# Power_Measurement.net
KiCad netlist of a schematic drawn in Altium Designer
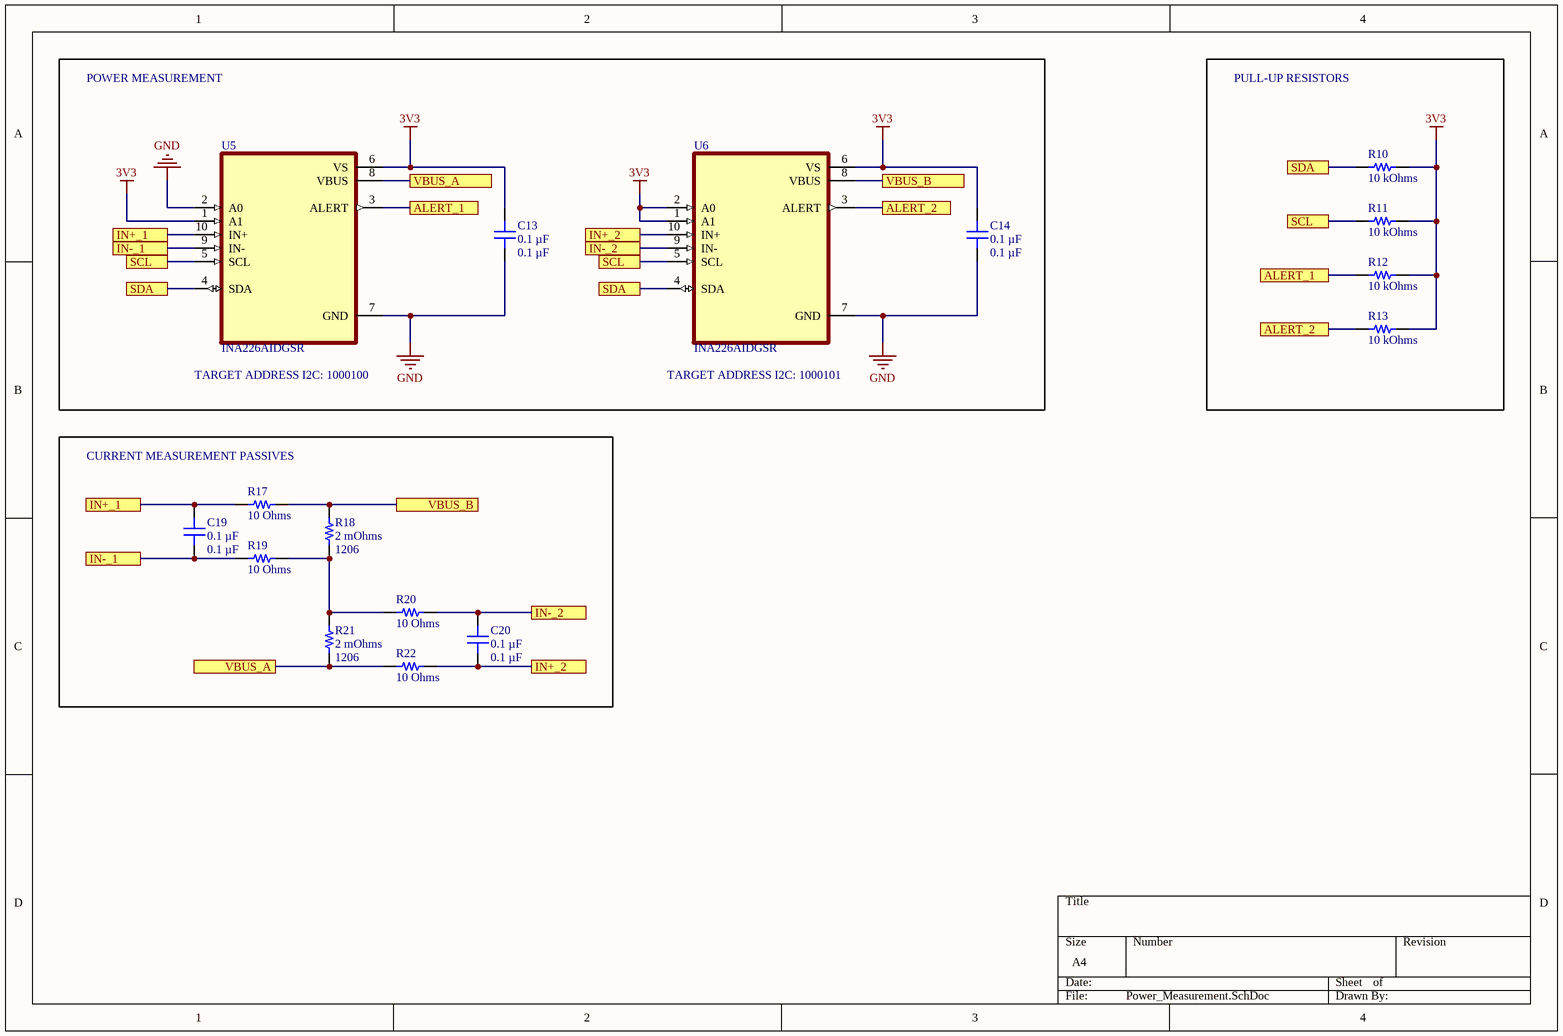
[diagram p0: Power_Measurement.SchDoc]

(export (version "E")
  (design (tool "Eeschema 10.0.6"))
  (components
    (comp (ref "C13")
      (value "0.1 µF")
      (footprint "CAP 0603_1608")
      (description "CAP CER 0.1UF 50V X7R 0603")
      (fields
        (field (name "PART NUMBER") "C0603C104K5RAC7411")
        (field (name "ALTIUM_VALUE") "0.1 µF")
        (field (name "MANUFACTURER") "KEMET")
      )
      (libsource (lib "Celestial Altium Library - altium_library") (part "Capacitor"))
    )
    (comp (ref "C14")
      (value "0.1 µF")
      (footprint "CAP 0603_1608")
      (description "CAP CER 0.1UF 50V X7R 0603")
      (fields
        (field (name "PART NUMBER") "C0603C104K5RAC7411")
        (field (name "ALTIUM_VALUE") "0.1 µF")
        (field (name "MANUFACTURER") "KEMET")
      )
      (libsource (lib "Celestial Altium Library - altium_library") (part "Capacitor"))
    )
    (comp (ref "C19")
      (value "0.1 µF")
      (footprint "CAP 0603_1608")
      (description "CAP CER 0.1UF 50V X7R 0603")
      (fields
        (field (name "PART NUMBER") "C0603C104K5RAC7411")
        (field (name "ALTIUM_VALUE") "0.1 µF")
        (field (name "MANUFACTURER") "KEMET")
      )
      (libsource (lib "Celestial Altium Library - altium_library") (part "Capacitor"))
    )
    (comp (ref "C20")
      (value "0.1 µF")
      (footprint "CAP 0603_1608")
      (description "CAP CER 0.1UF 50V X7R 0603")
      (fields
        (field (name "PART NUMBER") "C0603C104K5RAC7411")
        (field (name "ALTIUM_VALUE") "0.1 µF")
        (field (name "MANUFACTURER") "KEMET")
      )
      (libsource (lib "Celestial Altium Library - altium_library") (part "Capacitor"))
    )
    (comp (ref "R10")
      (value "10 kOhms")
      (footprint "RES 0603_1608")
      (description "RES 10K OHM 0.1% 1/16W 0603")
      (fields
        (field (name "PART NUMBER") "RNCS0603BKE10K0")
        (field (name "MANUFACTURER") "Stackpole Electronics Inc")
      )
      (libsource (lib "Celestial Altium Library - altium_library") (part "Resistor"))
    )
    (comp (ref "R11")
      (value "10 kOhms")
      (footprint "RES 0603_1608")
      (description "RES 10K OHM 0.1% 1/16W 0603")
      (fields
        (field (name "PART NUMBER") "RNCS0603BKE10K0")
        (field (name "MANUFACTURER") "Stackpole Electronics Inc")
      )
      (libsource (lib "Celestial Altium Library - altium_library") (part "Resistor"))
    )
    (comp (ref "R12")
      (value "10 kOhms")
      (footprint "RES 0603_1608")
      (description "RES 10K OHM 0.1% 1/16W 0603")
      (fields
        (field (name "PART NUMBER") "RNCS0603BKE10K0")
        (field (name "MANUFACTURER") "Stackpole Electronics Inc")
      )
      (libsource (lib "Celestial Altium Library - altium_library") (part "Resistor"))
    )
    (comp (ref "R13")
      (value "10 kOhms")
      (footprint "RES 0603_1608")
      (description "RES 10K OHM 0.1% 1/16W 0603")
      (fields
        (field (name "PART NUMBER") "RNCS0603BKE10K0")
        (field (name "MANUFACTURER") "Stackpole Electronics Inc")
      )
      (libsource (lib "Celestial Altium Library - altium_library") (part "Resistor"))
    )
    (comp (ref "R17")
      (value "10 Ohms")
      (footprint "RES 0603_1608")
      (description "RES SMD 10 OHM 0.1% 1/10W 0603")
      (fields (field (name "PART NUMBER") "CRT0603-BY-10R0ELF") (field (name "MANUFACTURER") "Bourns Inc."))
      (libsource (lib "Celestial Altium Library - altium_library") (part "Resistor"))
    )
    (comp (ref "R18")
      (value "2 mOhms")
      (footprint "STACKPOLE CSR1206")
      (description "1W 0.002 OHMS 1% 1206")
      (fields
        (field (name "PART NUMBER") "PCS1206FR0020ET")
        (field (name "PACKAGE / CASE") "1206")
        (field (name "MANUFACTURER") "Ohmite")
      )
      (libsource (lib "Celestial Altium Library - altium_library") (part "Resistor"))
    )
    (comp (ref "R19")
      (value "10 Ohms")
      (footprint "RES 0603_1608")
      (description "RES SMD 10 OHM 0.1% 1/10W 0603")
      (fields (field (name "PART NUMBER") "CRT0603-BY-10R0ELF") (field (name "MANUFACTURER") "Bourns Inc."))
      (libsource (lib "Celestial Altium Library - altium_library") (part "Resistor"))
    )
    (comp (ref "R20")
      (value "10 Ohms")
      (footprint "RES 0603_1608")
      (description "RES SMD 10 OHM 0.1% 1/10W 0603")
      (fields (field (name "PART NUMBER") "CRT0603-BY-10R0ELF") (field (name "MANUFACTURER") "Bourns Inc."))
      (libsource (lib "Celestial Altium Library - altium_library") (part "Resistor"))
    )
    (comp (ref "R21")
      (value "2 mOhms")
      (footprint "STACKPOLE CSR1206")
      (description "1W 0.002 OHMS 1% 1206")
      (fields
        (field (name "PART NUMBER") "PCS1206FR0020ET")
        (field (name "PACKAGE / CASE") "1206")
        (field (name "MANUFACTURER") "Ohmite")
      )
      (libsource (lib "Celestial Altium Library - altium_library") (part "Resistor"))
    )
    (comp (ref "R22")
      (value "10 Ohms")
      (footprint "RES 0603_1608")
      (description "RES SMD 10 OHM 0.1% 1/10W 0603")
      (fields (field (name "PART NUMBER") "CRT0603-BY-10R0ELF") (field (name "MANUFACTURER") "Bourns Inc."))
      (libsource (lib "Celestial Altium Library - altium_library") (part "Resistor"))
    )
    (comp (ref "U5")
      (value "INA226AIDGSR")
      (footprint "INA226AIDGSR:SOP50P490X110-10N")
      (fields (field (name "MF") "{'manufacturer': u'Texas Instruments'}"))
      (libsource (lib "*") (part "INA226AIDGSR"))
    )
    (comp (ref "U6")
      (value "INA226AIDGSR")
      (footprint "INA226AIDGSR:SOP50P490X110-10N")
      (fields (field (name "MF") "{'manufacturer': u'Texas Instruments'}"))
      (libsource (lib "*") (part "INA226AIDGSR"))
    )
  )
  (nets
    (net (code "1") (name "/ALERT_1") (class "Default")
      (node (ref "R12") (pin "2") (pinfunction "2_2") (pintype "passive"))
      (node (ref "U5") (pin "3") (pinfunction "ALERT_3") (pintype "output"))
    )
    (net (code "2") (name "/ALERT_2") (class "Default")
      (node (ref "R13") (pin "2") (pinfunction "2_2") (pintype "passive"))
      (node (ref "U6") (pin "3") (pinfunction "ALERT_3") (pintype "output"))
    )
    (net (code "3") (name "/IN+_1") (class "Default")
      (node (ref "C19") (pin "2") (pinfunction "2_2") (pintype "passive"))
      (node (ref "R17") (pin "2") (pinfunction "2_2") (pintype "passive"))
      (node (ref "U5") (pin "10") (pinfunction "IN+_10") (pintype "input"))
    )
    (net (code "4") (name "/IN+_2") (class "Default")
      (node (ref "C20") (pin "2") (pinfunction "2_2") (pintype "passive"))
      (node (ref "R22") (pin "2") (pinfunction "2_2") (pintype "passive"))
      (node (ref "U6") (pin "10") (pinfunction "IN+_10") (pintype "input"))
    )
    (net (code "5") (name "/IN-_1") (class "Default")
      (node (ref "C19") (pin "1") (pinfunction "1_1") (pintype "passive"))
      (node (ref "R19") (pin "2") (pinfunction "2_2") (pintype "passive"))
      (node (ref "U5") (pin "9") (pinfunction "IN-_9") (pintype "input"))
    )
    (net (code "6") (name "/IN-_2") (class "Default")
      (node (ref "C20") (pin "1") (pinfunction "1_1") (pintype "passive"))
      (node (ref "R20") (pin "2") (pinfunction "2_2") (pintype "passive"))
      (node (ref "U6") (pin "9") (pinfunction "IN-_9") (pintype "input"))
    )
    (net (code "7") (name "/SCL") (class "Default")
      (node (ref "R11") (pin "2") (pinfunction "2_2") (pintype "passive"))
      (node (ref "U5") (pin "5") (pinfunction "SCL_5") (pintype "input"))
      (node (ref "U6") (pin "5") (pinfunction "SCL_5") (pintype "input"))
    )
    (net (code "8") (name "/SDA") (class "Default")
      (node (ref "R10") (pin "2") (pinfunction "2_2") (pintype "passive"))
      (node (ref "U5") (pin "4") (pinfunction "SDA_4") (pintype "bidirectional"))
      (node (ref "U6") (pin "4") (pinfunction "SDA_4") (pintype "bidirectional"))
    )
    (net (code "9") (name "/VBUS_A") (class "Default")
      (node (ref "R21") (pin "1") (pinfunction "1_1") (pintype "passive"))
      (node (ref "R22") (pin "1") (pinfunction "1_1") (pintype "passive"))
      (node (ref "U5") (pin "8") (pinfunction "VBUS_8") (pintype "power_in"))
    )
    (net (code "10") (name "/VBUS_B") (class "Default")
      (node (ref "R17") (pin "1") (pinfunction "1_1") (pintype "passive"))
      (node (ref "R18") (pin "2") (pinfunction "2_2") (pintype "passive"))
      (node (ref "U6") (pin "8") (pinfunction "VBUS_8") (pintype "power_in"))
    )
    (net (code "11") (name "3V3") (class "Default")
      (node (ref "C13") (pin "1") (pinfunction "1_1") (pintype "passive"))
      (node (ref "C14") (pin "2") (pinfunction "2_2") (pintype "passive"))
      (node (ref "R10") (pin "1") (pinfunction "1_1") (pintype "passive"))
      (node (ref "R11") (pin "1") (pinfunction "1_1") (pintype "passive"))
      (node (ref "R12") (pin "1") (pinfunction "1_1") (pintype "passive"))
      (node (ref "R13") (pin "1") (pinfunction "1_1") (pintype "passive"))
      (node (ref "U5") (pin "1") (pinfunction "A1_1") (pintype "input"))
      (node (ref "U5") (pin "6") (pinfunction "VS_6") (pintype "power_in"))
      (node (ref "U6") (pin "1") (pinfunction "A1_1") (pintype "input"))
      (node (ref "U6") (pin "2") (pinfunction "A0_2") (pintype "input"))
      (node (ref "U6") (pin "6") (pinfunction "VS_6") (pintype "power_in"))
    )
    (net (code "12") (name "GND") (class "Default")
      (node (ref "C13") (pin "2") (pinfunction "2_2") (pintype "passive"))
      (node (ref "C14") (pin "1") (pinfunction "1_1") (pintype "passive"))
      (node (ref "U5") (pin "2") (pinfunction "A0_2") (pintype "input"))
      (node (ref "U5") (pin "7") (pinfunction "GND_7") (pintype "power_in"))
      (node (ref "U6") (pin "7") (pinfunction "GND_7") (pintype "power_in"))
    )
    (net (code "13") (name "Net-(R18-Pad1)") (class "Default")
      (node (ref "R18") (pin "1") (pinfunction "1_1") (pintype "passive"))
      (node (ref "R19") (pin "1") (pinfunction "1_1") (pintype "passive"))
      (node (ref "R20") (pin "1") (pinfunction "1_1") (pintype "passive"))
      (node (ref "R21") (pin "2") (pinfunction "2_2") (pintype "passive"))
    )
  )
)
